# 130731_AriloRX_0_0.net
KiCad netlist of a schematic drawn in EAGLE
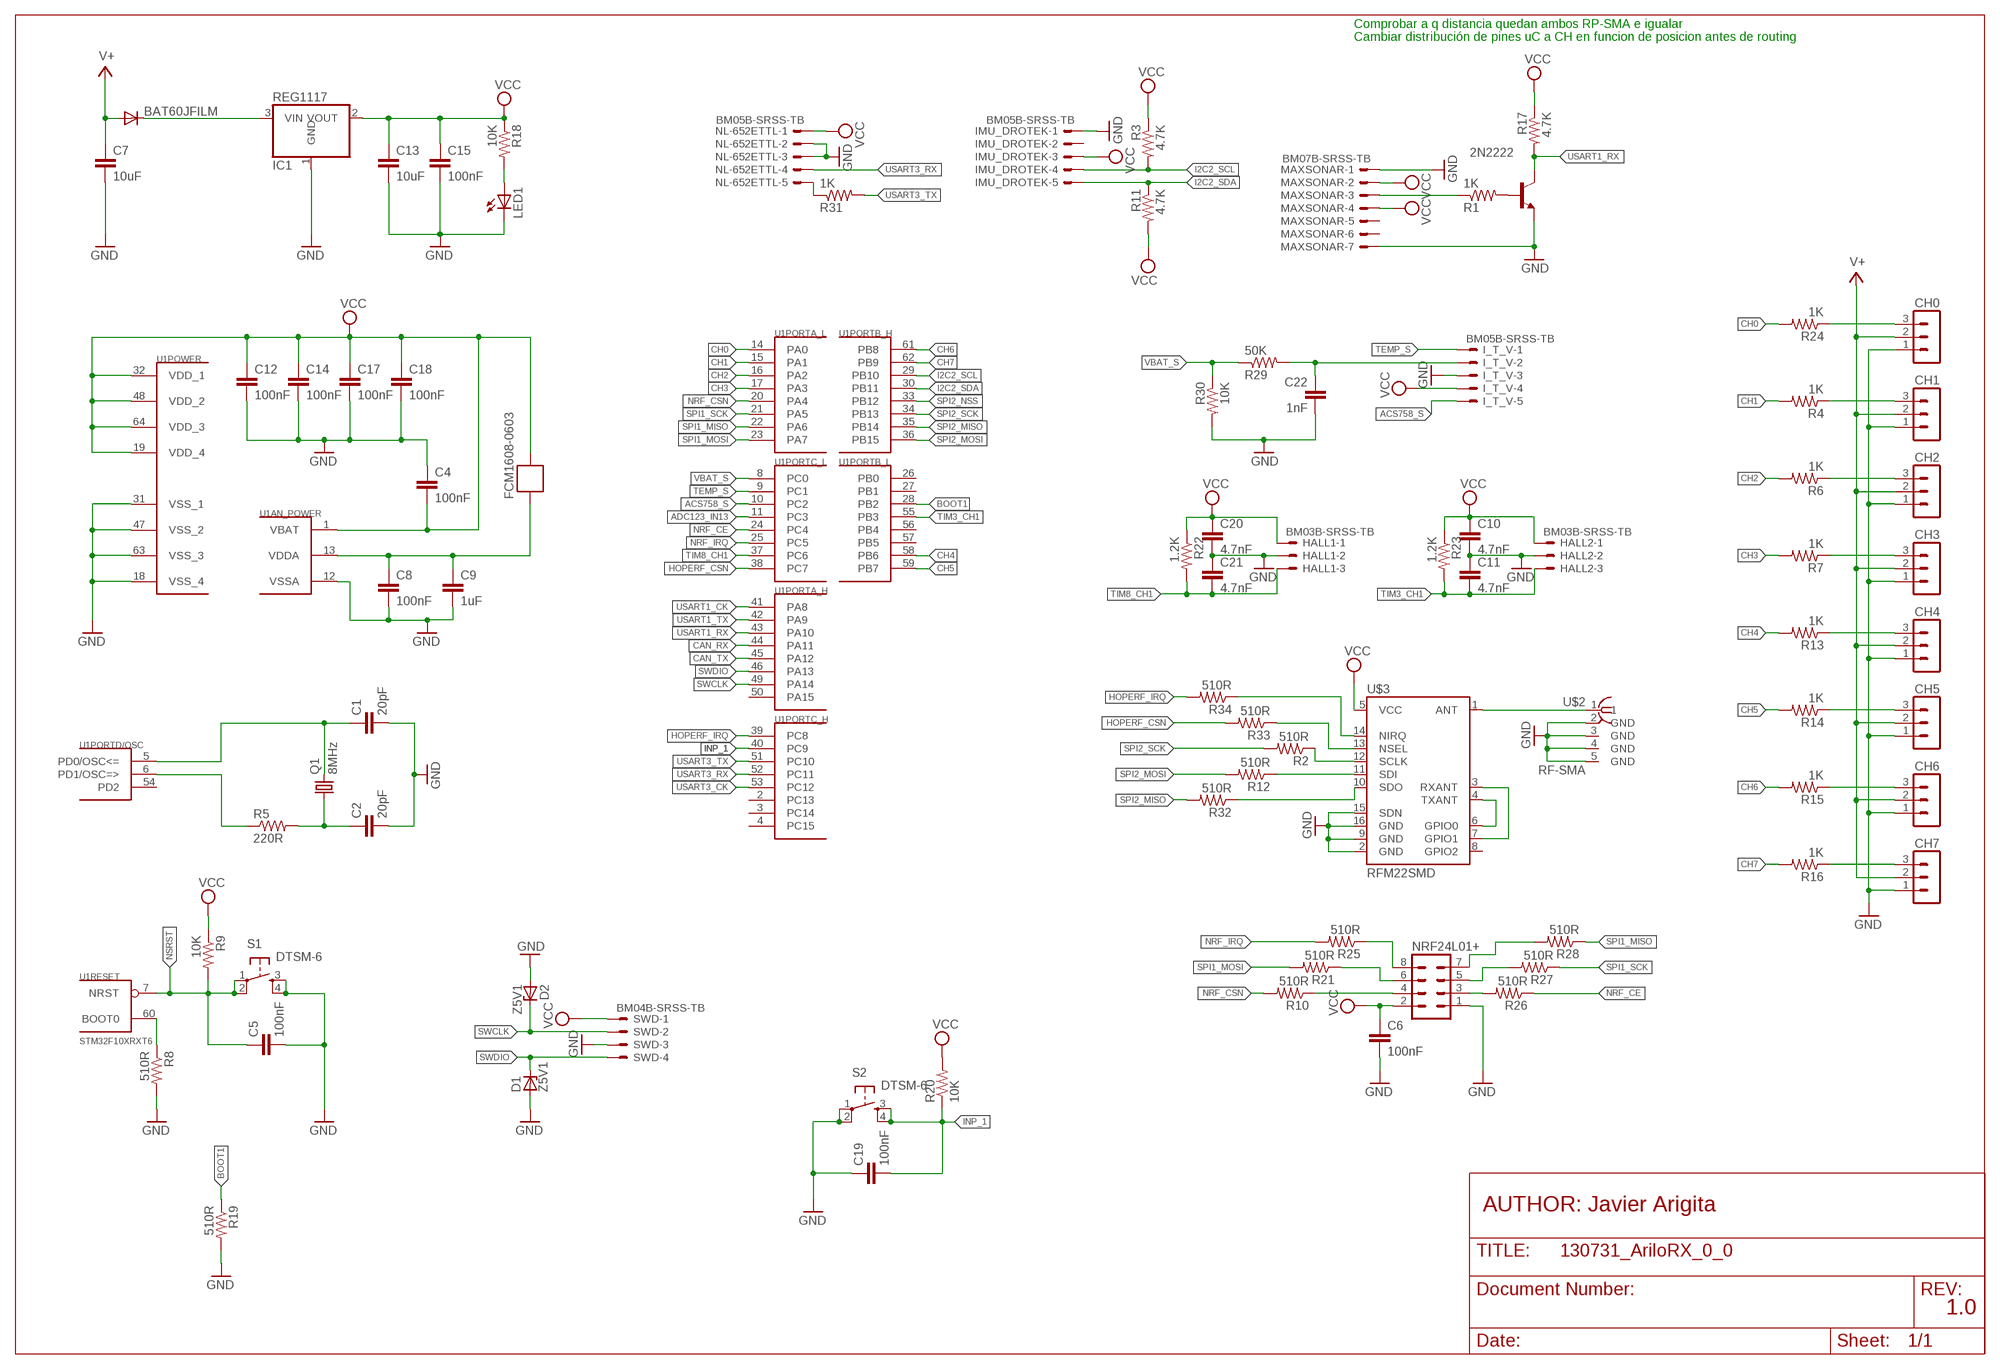
[diagram p0: schematic, sheet 1]

(export (version "E")
  (design (tool "Eeschema 10.0.6"))
  (components
    (comp (ref "2N2222")
      (value "MMBT2222ALT1-NPN-SOT23-BEC")
      (footprint "eagle-import:SOT23-BEC")
      (libsource (lib "eagle-import") (part "-NPN-SOT23-BECMMBT2222ALT1"))
    )
    (comp (ref "BAT60JFILM")
      (value "DIODE-SOD323-R")
      (footprint "eagle-import:SOD323-R")
      (libsource (lib "eagle-import") (part "DIODE-SOD323-R"))
    )
    (comp (ref "C1")
      (value "20pF")
      (footprint "eagle-import:C0805")
      (libsource (lib "eagle-import") (part "C-EUC0805"))
    )
    (comp (ref "C2")
      (value "20pF")
      (footprint "eagle-import:C0805")
      (libsource (lib "eagle-import") (part "C-EUC0805"))
    )
    (comp (ref "C4")
      (value "100nF")
      (footprint "eagle-import:C0805")
      (libsource (lib "eagle-import") (part "C-EUC0805"))
    )
    (comp (ref "C5")
      (value "100nF")
      (footprint "eagle-import:C0805")
      (libsource (lib "eagle-import") (part "C-EUC0805"))
    )
    (comp (ref "C6")
      (value "100nF")
      (footprint "eagle-import:C0805")
      (libsource (lib "eagle-import") (part "C-EUC0805"))
    )
    (comp (ref "C7")
      (value "10uF")
      (footprint "eagle-import:C3216")
      (libsource (lib "eagle-import") (part "resistor_C-EUC3216"))
    )
    (comp (ref "C8")
      (value "100nF")
      (footprint "eagle-import:C0805")
      (libsource (lib "eagle-import") (part "C-EUC0805"))
    )
    (comp (ref "C9")
      (value "1uF")
      (footprint "eagle-import:C3216")
      (libsource (lib "eagle-import") (part "resistor_C-EUC3216"))
    )
    (comp (ref "C10")
      (value "4.7nF")
      (footprint "eagle-import:C0805")
      (libsource (lib "eagle-import") (part "C-EUC0805"))
    )
    (comp (ref "C11")
      (value "4.7nF")
      (footprint "eagle-import:C0805")
      (libsource (lib "eagle-import") (part "C-EUC0805"))
    )
    (comp (ref "C12")
      (value "100nF")
      (footprint "eagle-import:C0805")
      (libsource (lib "eagle-import") (part "C-EUC0805"))
    )
    (comp (ref "C13")
      (value "10uF")
      (footprint "eagle-import:C3216")
      (libsource (lib "eagle-import") (part "resistor_C-EUC3216"))
    )
    (comp (ref "C14")
      (value "100nF")
      (footprint "eagle-import:C0805")
      (libsource (lib "eagle-import") (part "C-EUC0805"))
    )
    (comp (ref "C15")
      (value "100nF")
      (footprint "eagle-import:C0805")
      (libsource (lib "eagle-import") (part "C-EUC0805"))
    )
    (comp (ref "C17")
      (value "100nF")
      (footprint "eagle-import:C0805")
      (libsource (lib "eagle-import") (part "C-EUC0805"))
    )
    (comp (ref "C18")
      (value "100nF")
      (footprint "eagle-import:C0805")
      (libsource (lib "eagle-import") (part "C-EUC0805"))
    )
    (comp (ref "C19")
      (value "100nF")
      (footprint "eagle-import:C0805")
      (libsource (lib "eagle-import") (part "C-EUC0805"))
    )
    (comp (ref "C20")
      (value "4.7nF")
      (footprint "eagle-import:C0805")
      (libsource (lib "eagle-import") (part "C-EUC0805"))
    )
    (comp (ref "C21")
      (value "4.7nF")
      (footprint "eagle-import:C0805")
      (libsource (lib "eagle-import") (part "C-EUC0805"))
    )
    (comp (ref "C22")
      (value "1nF")
      (footprint "eagle-import:C0805")
      (libsource (lib "eagle-import") (part "C-EUC0805"))
    )
    (comp (ref "CH0")
      (value "MA03-1")
      (footprint "eagle-import:MA03-1")
      (libsource (lib "eagle-import") (part "MA03-1"))
    )
    (comp (ref "CH1")
      (value "MA03-1")
      (footprint "eagle-import:MA03-1")
      (libsource (lib "eagle-import") (part "MA03-1"))
    )
    (comp (ref "CH2")
      (value "MA03-1")
      (footprint "eagle-import:MA03-1")
      (libsource (lib "eagle-import") (part "MA03-1"))
    )
    (comp (ref "CH3")
      (value "MA03-1")
      (footprint "eagle-import:MA03-1")
      (libsource (lib "eagle-import") (part "MA03-1"))
    )
    (comp (ref "CH4")
      (value "MA03-1")
      (footprint "eagle-import:MA03-1")
      (libsource (lib "eagle-import") (part "MA03-1"))
    )
    (comp (ref "CH5")
      (value "MA03-1")
      (footprint "eagle-import:MA03-1")
      (libsource (lib "eagle-import") (part "MA03-1"))
    )
    (comp (ref "CH6")
      (value "MA03-1")
      (footprint "eagle-import:MA03-1")
      (libsource (lib "eagle-import") (part "MA03-1"))
    )
    (comp (ref "CH7")
      (value "MA03-1")
      (footprint "eagle-import:MA03-1")
      (libsource (lib "eagle-import") (part "MA03-1"))
    )
    (comp (ref "D1")
      (value "Z5V1")
      (footprint "eagle-import:SOD80C")
      (libsource (lib "eagle-import") (part "ZENER-DIODESOD80C"))
    )
    (comp (ref "D2")
      (value "Z5V1")
      (footprint "eagle-import:SOD80C")
      (libsource (lib "eagle-import") (part "ZENER-DIODESOD80C"))
    )
    (comp (ref "FCM1608-0603")
      (value "FERRITE-BEAD")
      (footprint "eagle-import:R0603")
      (libsource (lib "eagle-import") (part "FERRITE-BEAD"))
    )
    (comp (ref "HALL1")
      (value "BM03B-SRSS-TB")
      (footprint "eagle-import:BM03B-SRSS-TB")
      (libsource (lib "eagle-import") (part "?M03B-SRSS-TBB"))
    )
    (comp (ref "HALL2")
      (value "BM03B-SRSS-TB")
      (footprint "eagle-import:BM03B-SRSS-TB")
      (libsource (lib "eagle-import") (part "?M03B-SRSS-TBB"))
    )
    (comp (ref "IC1")
      (value "REG1117")
      (footprint "eagle-import:SOT223")
      (libsource (lib "eagle-import") (part "REG1117"))
    )
    (comp (ref "IMU_DROTEK")
      (value "BM05B-SRSS-TB")
      (footprint "eagle-import:BM05B-SRSS-TB")
      (libsource (lib "eagle-import") (part "?M05B-SRSS-TBB"))
    )
    (comp (ref "I_T_V")
      (value "BM05B-SRSS-TB")
      (footprint "eagle-import:BM05B-SRSS-TB")
      (libsource (lib "eagle-import") (part "?M05B-SRSS-TBB"))
    )
    (comp (ref "LED1")
      (value "LED0805")
      (footprint "eagle-import:CHIPLED_0805")
      (libsource (lib "eagle-import") (part "LED0805"))
    )
    (comp (ref "MAXSONAR")
      (value "BM07B-SRSS-TB")
      (footprint "eagle-import:BM07B-SRSS-TB")
      (libsource (lib "eagle-import") (part "?M07B-SRSS-TBB"))
    )
    (comp (ref "NL-652ETTL")
      (value "BM05B-SRSS-TB")
      (footprint "eagle-import:BM05B-SRSS-TB")
      (libsource (lib "eagle-import") (part "?M05B-SRSS-TBB"))
    )
    (comp (ref "NRF24L01+")
      (value "MA04-2")
      (footprint "eagle-import:MA04-2")
      (libsource (lib "eagle-import") (part "MA04-2"))
    )
    (comp (ref "Q1")
      (value "8MHz")
      (footprint "eagle-import:SM49")
      (libsource (lib "eagle-import") (part "CRYSTALSM49"))
    )
    (comp (ref "R1")
      (value "1K")
      (footprint "eagle-import:R0805")
      (libsource (lib "eagle-import") (part "RESISTOR0805"))
    )
    (comp (ref "R2")
      (value "510R")
      (footprint "eagle-import:R0805")
      (libsource (lib "eagle-import") (part "RESISTOR0805"))
    )
    (comp (ref "R3")
      (value "4.7K")
      (footprint "eagle-import:R0805")
      (libsource (lib "eagle-import") (part "RESISTOR0805"))
    )
    (comp (ref "R4")
      (value "1K")
      (footprint "eagle-import:R0805")
      (libsource (lib "eagle-import") (part "RESISTOR0805"))
    )
    (comp (ref "R5")
      (value "220R")
      (footprint "eagle-import:R0805")
      (libsource (lib "eagle-import") (part "RESISTOR0805"))
    )
    (comp (ref "R6")
      (value "1K")
      (footprint "eagle-import:R0805")
      (libsource (lib "eagle-import") (part "RESISTOR0805"))
    )
    (comp (ref "R7")
      (value "1K")
      (footprint "eagle-import:R0805")
      (libsource (lib "eagle-import") (part "RESISTOR0805"))
    )
    (comp (ref "R8")
      (value "510R")
      (footprint "eagle-import:R0805")
      (libsource (lib "eagle-import") (part "RESISTOR0805"))
    )
    (comp (ref "R9")
      (value "10K")
      (footprint "eagle-import:R0805")
      (libsource (lib "eagle-import") (part "RESISTOR0805"))
    )
    (comp (ref "R10")
      (value "510R")
      (footprint "eagle-import:R0805")
      (libsource (lib "eagle-import") (part "RESISTOR0805"))
    )
    (comp (ref "R11")
      (value "4.7K")
      (footprint "eagle-import:R0805")
      (libsource (lib "eagle-import") (part "RESISTOR0805"))
    )
    (comp (ref "R12")
      (value "510R")
      (footprint "eagle-import:R0805")
      (libsource (lib "eagle-import") (part "RESISTOR0805"))
    )
    (comp (ref "R13")
      (value "1K")
      (footprint "eagle-import:R0805")
      (libsource (lib "eagle-import") (part "RESISTOR0805"))
    )
    (comp (ref "R14")
      (value "1K")
      (footprint "eagle-import:R0805")
      (libsource (lib "eagle-import") (part "RESISTOR0805"))
    )
    (comp (ref "R15")
      (value "1K")
      (footprint "eagle-import:R0805")
      (libsource (lib "eagle-import") (part "RESISTOR0805"))
    )
    (comp (ref "R16")
      (value "1K")
      (footprint "eagle-import:R0805")
      (libsource (lib "eagle-import") (part "RESISTOR0805"))
    )
    (comp (ref "R17")
      (value "4.7K")
      (footprint "eagle-import:R0805")
      (libsource (lib "eagle-import") (part "RESISTOR0805"))
    )
    (comp (ref "R18")
      (value "10K")
      (footprint "eagle-import:R0805")
      (libsource (lib "eagle-import") (part "RESISTOR0805"))
    )
    (comp (ref "R19")
      (value "510R")
      (footprint "eagle-import:R0805")
      (libsource (lib "eagle-import") (part "RESISTOR0805"))
    )
    (comp (ref "R20")
      (value "10K")
      (footprint "eagle-import:R0805")
      (libsource (lib "eagle-import") (part "RESISTOR0805"))
    )
    (comp (ref "R21")
      (value "510R")
      (footprint "eagle-import:R0805")
      (libsource (lib "eagle-import") (part "RESISTOR0805"))
    )
    (comp (ref "R22")
      (value "1.2K")
      (footprint "eagle-import:R0805")
      (libsource (lib "eagle-import") (part "RESISTOR0805"))
    )
    (comp (ref "R23")
      (value "1.2K")
      (footprint "eagle-import:R0805")
      (libsource (lib "eagle-import") (part "RESISTOR0805"))
    )
    (comp (ref "R24")
      (value "1K")
      (footprint "eagle-import:R0805")
      (libsource (lib "eagle-import") (part "RESISTOR0805"))
    )
    (comp (ref "R25")
      (value "510R")
      (footprint "eagle-import:R0805")
      (libsource (lib "eagle-import") (part "RESISTOR0805"))
    )
    (comp (ref "R26")
      (value "510R")
      (footprint "eagle-import:R0805")
      (libsource (lib "eagle-import") (part "RESISTOR0805"))
    )
    (comp (ref "R27")
      (value "510R")
      (footprint "eagle-import:R0805")
      (libsource (lib "eagle-import") (part "RESISTOR0805"))
    )
    (comp (ref "R28")
      (value "510R")
      (footprint "eagle-import:R0805")
      (libsource (lib "eagle-import") (part "RESISTOR0805"))
    )
    (comp (ref "R29")
      (value "50K")
      (footprint "eagle-import:R0805")
      (libsource (lib "eagle-import") (part "RESISTOR0805"))
    )
    (comp (ref "R30")
      (value "10K")
      (footprint "eagle-import:R0805")
      (libsource (lib "eagle-import") (part "RESISTOR0805"))
    )
    (comp (ref "R31")
      (value "1K")
      (footprint "eagle-import:R0805")
      (libsource (lib "eagle-import") (part "RESISTOR0805"))
    )
    (comp (ref "R32")
      (value "510R")
      (footprint "eagle-import:R0805")
      (libsource (lib "eagle-import") (part "RESISTOR0805"))
    )
    (comp (ref "R33")
      (value "510R")
      (footprint "eagle-import:R0805")
      (libsource (lib "eagle-import") (part "RESISTOR0805"))
    )
    (comp (ref "R34")
      (value "510R")
      (footprint "eagle-import:R0805")
      (libsource (lib "eagle-import") (part "RESISTOR0805"))
    )
    (comp (ref "S1")
      (value "DTSM-6")
      (footprint "eagle-import:DTSM-6")
      (libsource (lib "eagle-import") (part "DTSM-6"))
    )
    (comp (ref "S2")
      (value "DTSM-6")
      (footprint "eagle-import:DTSM-6")
      (libsource (lib "eagle-import") (part "DTSM-6"))
    )
    (comp (ref "SWD")
      (value "BM04B-SRSS-TB")
      (footprint "eagle-import:BM04B-SRSS-TB")
      (libsource (lib "eagle-import") (part "?M04B-SRSS-TBB"))
    )
    (comp (ref "U$2")
      (value "RF-SMA")
      (footprint "eagle-import:BU-SMA-H")
      (libsource (lib "eagle-import") (part "RF-SMA"))
    )
    (comp (ref "U$3")
      (value "RFM22SMD")
      (footprint "eagle-import:RFM22-XXX-S2")
      (libsource (lib "eagle-import") (part "RFM22SMD"))
    )
    (comp (ref "U1")
      (value "STM32F10XRXT6")
      (footprint "eagle-import:TQFP64")
      (libsource (lib "eagle-import") (part "STM32F10XRXT6"))
    )
  )
  (nets
    (net (code "1") (name "ACS758_S") (class "Default")
      (node (ref "I_T_V") (pin "5") (pinfunction "S_5") (pintype "passive"))
      (node (ref "U1") (pin "10") (pinfunction "PC2_10") (pintype "bidirectional"))
    )
    (net (code "2") (name "ADC123_IN13") (class "Default")
      (node (ref "U1") (pin "11") (pinfunction "PC3_11") (pintype "bidirectional"))
    )
    (net (code "3") (name "BOOT1") (class "Default")
      (node (ref "R19") (pin "1") (pinfunction "1_1") (pintype "passive"))
      (node (ref "U1") (pin "28") (pinfunction "PB2_28") (pintype "bidirectional"))
    )
    (net (code "4") (name "CAN_RX") (class "Default")
      (node (ref "U1") (pin "44") (pinfunction "PA11_44") (pintype "bidirectional"))
    )
    (net (code "5") (name "CAN_TX") (class "Default")
      (node (ref "U1") (pin "45") (pinfunction "PA12_45") (pintype "bidirectional"))
    )
    (net (code "6") (name "CH0") (class "Default")
      (node (ref "R24") (pin "2") (pinfunction "2_2") (pintype "passive"))
      (node (ref "U1") (pin "14") (pinfunction "PA0_14") (pintype "bidirectional"))
    )
    (net (code "7") (name "CH1") (class "Default")
      (node (ref "R4") (pin "2") (pinfunction "2_2") (pintype "passive"))
      (node (ref "U1") (pin "15") (pinfunction "PA1_15") (pintype "bidirectional"))
    )
    (net (code "8") (name "CH2") (class "Default")
      (node (ref "R6") (pin "2") (pinfunction "2_2") (pintype "passive"))
      (node (ref "U1") (pin "16") (pinfunction "PA2_16") (pintype "bidirectional"))
    )
    (net (code "9") (name "CH3") (class "Default")
      (node (ref "R7") (pin "2") (pinfunction "2_2") (pintype "passive"))
      (node (ref "U1") (pin "17") (pinfunction "PA3_17") (pintype "bidirectional"))
    )
    (net (code "10") (name "CH4") (class "Default")
      (node (ref "R13") (pin "2") (pinfunction "2_2") (pintype "passive"))
      (node (ref "U1") (pin "58") (pinfunction "PB6_58") (pintype "bidirectional"))
    )
    (net (code "11") (name "CH5") (class "Default")
      (node (ref "R14") (pin "2") (pinfunction "2_2") (pintype "passive"))
      (node (ref "U1") (pin "59") (pinfunction "PB7_59") (pintype "bidirectional"))
    )
    (net (code "12") (name "CH6") (class "Default")
      (node (ref "R15") (pin "2") (pinfunction "2_2") (pintype "passive"))
      (node (ref "U1") (pin "61") (pinfunction "PB8_61") (pintype "bidirectional"))
    )
    (net (code "13") (name "CH7") (class "Default")
      (node (ref "R16") (pin "2") (pinfunction "2_2") (pintype "passive"))
      (node (ref "U1") (pin "62") (pinfunction "PB9_62") (pintype "bidirectional"))
    )
    (net (code "14") (name "GND") (class "Default")
      (node (ref "2N2222") (pin "E") (pinfunction "E_E") (pintype "passive"))
      (node (ref "C1") (pin "2") (pinfunction "2_2") (pintype "passive"))
      (node (ref "C10") (pin "2") (pinfunction "2_2") (pintype "passive"))
      (node (ref "C11") (pin "1") (pinfunction "1_1") (pintype "passive"))
      (node (ref "C12") (pin "2") (pinfunction "2_2") (pintype "passive"))
      (node (ref "C13") (pin "2") (pinfunction "2_2") (pintype "passive"))
      (node (ref "C14") (pin "2") (pinfunction "2_2") (pintype "passive"))
      (node (ref "C15") (pin "2") (pinfunction "2_2") (pintype "passive"))
      (node (ref "C17") (pin "2") (pinfunction "2_2") (pintype "passive"))
      (node (ref "C18") (pin "2") (pinfunction "2_2") (pintype "passive"))
      (node (ref "C19") (pin "1") (pinfunction "1_1") (pintype "passive"))
      (node (ref "C2") (pin "2") (pinfunction "2_2") (pintype "passive"))
      (node (ref "C20") (pin "2") (pinfunction "2_2") (pintype "passive"))
      (node (ref "C21") (pin "1") (pinfunction "1_1") (pintype "passive"))
      (node (ref "C22") (pin "2") (pinfunction "2_2") (pintype "passive"))
      (node (ref "C4") (pin "1") (pinfunction "1_1") (pintype "passive"))
      (node (ref "C5") (pin "2") (pinfunction "2_2") (pintype "passive"))
      (node (ref "C6") (pin "2") (pinfunction "2_2") (pintype "passive"))
      (node (ref "C7") (pin "2") (pinfunction "2_2") (pintype "passive"))
      (node (ref "C8") (pin "2") (pinfunction "2_2") (pintype "passive"))
      (node (ref "C9") (pin "2") (pinfunction "2_2") (pintype "passive"))
      (node (ref "CH0") (pin "1") (pinfunction "1_1") (pintype "passive"))
      (node (ref "CH1") (pin "1") (pinfunction "1_1") (pintype "passive"))
      (node (ref "CH2") (pin "1") (pinfunction "1_1") (pintype "passive"))
      (node (ref "CH3") (pin "1") (pinfunction "1_1") (pintype "passive"))
      (node (ref "CH4") (pin "1") (pinfunction "1_1") (pintype "passive"))
      (node (ref "CH5") (pin "1") (pinfunction "1_1") (pintype "passive"))
      (node (ref "CH6") (pin "1") (pinfunction "1_1") (pintype "passive"))
      (node (ref "CH7") (pin "1") (pinfunction "1_1") (pintype "passive"))
      (node (ref "D1") (pin "A") (pinfunction "A_A") (pintype "passive"))
      (node (ref "D2") (pin "A") (pinfunction "A_A") (pintype "passive"))
      (node (ref "HALL1") (pin "2") (pinfunction "S_2") (pintype "passive"))
      (node (ref "HALL2") (pin "2") (pinfunction "S_2") (pintype "passive"))
      (node (ref "IC1") (pin "1") (pinfunction "GND_1") (pintype "power_in"))
      (node (ref "IMU_DROTEK") (pin "1") (pinfunction "S_1") (pintype "passive"))
      (node (ref "I_T_V") (pin "3") (pinfunction "S_3") (pintype "passive"))
      (node (ref "LED1") (pin "C") (pinfunction "C_C") (pintype "passive"))
      (node (ref "MAXSONAR") (pin "1") (pinfunction "S_1") (pintype "passive"))
      (node (ref "MAXSONAR") (pin "7") (pinfunction "S_7") (pintype "passive"))
      (node (ref "NL-652ETTL") (pin "2") (pinfunction "S_2") (pintype "passive"))
      (node (ref "NL-652ETTL") (pin "3") (pinfunction "S_3") (pintype "passive"))
      (node (ref "NRF24L01+") (pin "1") (pinfunction "1_1") (pintype "passive"))
      (node (ref "R19") (pin "2") (pinfunction "2_2") (pintype "passive"))
      (node (ref "R30") (pin "2") (pinfunction "2_2") (pintype "passive"))
      (node (ref "R8") (pin "2") (pinfunction "2_2") (pintype "passive"))
      (node (ref "S1") (pin "3") (pinfunction "3_3") (pintype "passive"))
      (node (ref "S1") (pin "4") (pinfunction "4_4") (pintype "passive"))
      (node (ref "S2") (pin "1") (pinfunction "1_1") (pintype "passive"))
      (node (ref "S2") (pin "2") (pinfunction "2_2") (pintype "passive"))
      (node (ref "SWD") (pin "3") (pinfunction "S_3") (pintype "passive"))
      (node (ref "U$2") (pin "2") (pinfunction "GND_2") (pintype "power_in"))
      (node (ref "U$2") (pin "3") (pinfunction "GND_3") (pintype "bidirectional"))
      (node (ref "U$2") (pin "4") (pinfunction "GND_4") (pintype "bidirectional"))
      (node (ref "U$2") (pin "5") (pinfunction "GND_5") (pintype "bidirectional"))
      (node (ref "U$3") (pin "15") (pinfunction "SDN_15") (pintype "input"))
      (node (ref "U$3") (pin "16") (pinfunction "GND_16") (pintype "power_in"))
      (node (ref "U$3") (pin "2") (pinfunction "GND_2") (pintype "power_in"))
      (node (ref "U$3") (pin "9") (pinfunction "GND_9") (pintype "power_in"))
      (node (ref "U1") (pin "12") (pinfunction "VSSA_12") (pintype "power_in"))
      (node (ref "U1") (pin "18") (pinfunction "VSS_4_18") (pintype "power_in"))
      (node (ref "U1") (pin "31") (pinfunction "VSS_1_31") (pintype "power_in"))
      (node (ref "U1") (pin "47") (pinfunction "VSS_2_47") (pintype "power_in"))
      (node (ref "U1") (pin "63") (pinfunction "VSS_3_63") (pintype "power_in"))
    )
    (net (code "15") (name "HOPERF_CSN") (class "Default")
      (node (ref "R33") (pin "2") (pinfunction "2_2") (pintype "passive"))
      (node (ref "U1") (pin "38") (pinfunction "PC7_38") (pintype "bidirectional"))
    )
    (net (code "16") (name "HOPERF_IRQ") (class "Default")
      (node (ref "R34") (pin "2") (pinfunction "2_2") (pintype "passive"))
      (node (ref "U1") (pin "39") (pinfunction "PC8_39") (pintype "bidirectional"))
    )
    (net (code "17") (name "I2C2_SCL") (class "Default")
      (node (ref "IMU_DROTEK") (pin "4") (pinfunction "S_4") (pintype "passive"))
      (node (ref "R3") (pin "2") (pinfunction "2_2") (pintype "passive"))
      (node (ref "U1") (pin "29") (pinfunction "PB10_29") (pintype "bidirectional"))
    )
    (net (code "18") (name "I2C2_SDA") (class "Default")
      (node (ref "IMU_DROTEK") (pin "5") (pinfunction "S_5") (pintype "passive"))
      (node (ref "R11") (pin "1") (pinfunction "1_1") (pintype "passive"))
      (node (ref "U1") (pin "30") (pinfunction "PB11_30") (pintype "bidirectional"))
    )
    (net (code "19") (name "INP_1") (class "Default")
      (node (ref "C19") (pin "2") (pinfunction "2_2") (pintype "passive"))
      (node (ref "R20") (pin "1") (pinfunction "1_1") (pintype "passive"))
      (node (ref "S2") (pin "3") (pinfunction "3_3") (pintype "passive"))
      (node (ref "S2") (pin "4") (pinfunction "4_4") (pintype "passive"))
      (node (ref "U1") (pin "40") (pinfunction "PC9_40") (pintype "bidirectional"))
    )
    (net (code "20") (name "NRF_CE") (class "Default")
      (node (ref "R26") (pin "1") (pinfunction "1_1") (pintype "passive"))
      (node (ref "U1") (pin "24") (pinfunction "PC4_24") (pintype "bidirectional"))
    )
    (net (code "21") (name "NRF_CSN") (class "Default")
      (node (ref "R10") (pin "2") (pinfunction "2_2") (pintype "passive"))
      (node (ref "U1") (pin "20") (pinfunction "PA4_20") (pintype "bidirectional"))
    )
    (net (code "22") (name "NRF_IRQ") (class "Default")
      (node (ref "R25") (pin "2") (pinfunction "2_2") (pintype "passive"))
      (node (ref "U1") (pin "25") (pinfunction "PC5_25") (pintype "bidirectional"))
    )
    (net (code "23") (name "NSRST") (class "Default")
      (node (ref "C5") (pin "1") (pinfunction "1_1") (pintype "passive"))
      (node (ref "R9") (pin "2") (pinfunction "2_2") (pintype "passive"))
      (node (ref "S1") (pin "1") (pinfunction "1_1") (pintype "passive"))
      (node (ref "S1") (pin "2") (pinfunction "2_2") (pintype "passive"))
      (node (ref "U1") (pin "7") (pinfunction "NRST_7") (pintype "input"))
    )
    (net (code "24") (name "Net-(2N2222-PadB)") (class "Default")
      (node (ref "2N2222") (pin "B") (pinfunction "B_B") (pintype "passive"))
      (node (ref "R1") (pin "2") (pinfunction "2_2") (pintype "passive"))
    )
    (net (code "25") (name "Net-(C2-Pad1)") (class "Default")
      (node (ref "C2") (pin "1") (pinfunction "1_1") (pintype "passive"))
      (node (ref "Q1") (pin "1") (pinfunction "1_1") (pintype "passive"))
      (node (ref "R5") (pin "2") (pinfunction "2_2") (pintype "passive"))
    )
    (net (code "26") (name "Net-(CH0-Pad3)") (class "Default")
      (node (ref "CH0") (pin "3") (pinfunction "3_3") (pintype "passive"))
      (node (ref "R24") (pin "1") (pinfunction "1_1") (pintype "passive"))
    )
    (net (code "27") (name "Net-(CH1-Pad3)") (class "Default")
      (node (ref "CH1") (pin "3") (pinfunction "3_3") (pintype "passive"))
      (node (ref "R4") (pin "1") (pinfunction "1_1") (pintype "passive"))
    )
    (net (code "28") (name "Net-(CH2-Pad3)") (class "Default")
      (node (ref "CH2") (pin "3") (pinfunction "3_3") (pintype "passive"))
      (node (ref "R6") (pin "1") (pinfunction "1_1") (pintype "passive"))
    )
    (net (code "29") (name "Net-(CH3-Pad3)") (class "Default")
      (node (ref "CH3") (pin "3") (pinfunction "3_3") (pintype "passive"))
      (node (ref "R7") (pin "1") (pinfunction "1_1") (pintype "passive"))
    )
    (net (code "30") (name "Net-(CH4-Pad3)") (class "Default")
      (node (ref "CH4") (pin "3") (pinfunction "3_3") (pintype "passive"))
      (node (ref "R13") (pin "1") (pinfunction "1_1") (pintype "passive"))
    )
    (net (code "31") (name "Net-(CH5-Pad3)") (class "Default")
      (node (ref "CH5") (pin "3") (pinfunction "3_3") (pintype "passive"))
      (node (ref "R14") (pin "1") (pinfunction "1_1") (pintype "passive"))
    )
    (net (code "32") (name "Net-(CH6-Pad3)") (class "Default")
      (node (ref "CH6") (pin "3") (pinfunction "3_3") (pintype "passive"))
      (node (ref "R15") (pin "1") (pinfunction "1_1") (pintype "passive"))
    )
    (net (code "33") (name "Net-(CH7-Pad3)") (class "Default")
      (node (ref "CH7") (pin "3") (pinfunction "3_3") (pintype "passive"))
      (node (ref "R16") (pin "1") (pinfunction "1_1") (pintype "passive"))
    )
    (net (code "34") (name "Net-(FCM1608-0603-P$2)") (class "Default")
      (node (ref "C8") (pin "1") (pinfunction "1_1") (pintype "passive"))
      (node (ref "C9") (pin "1") (pinfunction "1_1") (pintype "passive"))
      (node (ref "FCM1608-0603") (pin "2") (pinfunction "P$2_2") (pintype "bidirectional"))
      (node (ref "U1") (pin "13") (pinfunction "VDDA_13") (pintype "power_in"))
    )
    (net (code "35") (name "Net-(IC1-VIN)") (class "Default")
      (node (ref "BAT60JFILM") (pin "C") (pinfunction "C_C") (pintype "passive"))
      (node (ref "IC1") (pin "3") (pinfunction "VIN_3") (pintype "input"))
    )
    (net (code "36") (name "Net-(I_T_VB-S)") (class "Default")
      (node (ref "C22") (pin "1") (pinfunction "1_1") (pintype "passive"))
      (node (ref "I_T_V") (pin "2") (pinfunction "S_2") (pintype "passive"))
      (node (ref "R29") (pin "2") (pinfunction "2_2") (pintype "passive"))
    )
    (net (code "37") (name "Net-(LED1-PadA)") (class "Default")
      (node (ref "LED1") (pin "A") (pinfunction "A_A") (pintype "passive"))
      (node (ref "R18") (pin "2") (pinfunction "2_2") (pintype "passive"))
    )
    (net (code "38") (name "Net-(MAXSONARC-S)") (class "Default")
      (node (ref "MAXSONAR") (pin "3") (pinfunction "S_3") (pintype "passive"))
      (node (ref "R1") (pin "1") (pinfunction "1_1") (pintype "passive"))
    )
    (net (code "39") (name "Net-(NL-652ETTLE-S)") (class "Default")
      (node (ref "NL-652ETTL") (pin "5") (pinfunction "S_5") (pintype "passive"))
      (node (ref "R31") (pin "1") (pinfunction "1_1") (pintype "passive"))
    )
    (net (code "40") (name "Net-(NRF24L01+-Pad3)") (class "Default")
      (node (ref "NRF24L01+") (pin "3") (pinfunction "3_3") (pintype "passive"))
      (node (ref "R26") (pin "2") (pinfunction "2_2") (pintype "passive"))
    )
    (net (code "41") (name "Net-(NRF24L01+-Pad4)") (class "Default")
      (node (ref "NRF24L01+") (pin "4") (pinfunction "4_4") (pintype "passive"))
      (node (ref "R10") (pin "1") (pinfunction "1_1") (pintype "passive"))
    )
    (net (code "42") (name "Net-(NRF24L01+-Pad5)") (class "Default")
      (node (ref "NRF24L01+") (pin "5") (pinfunction "5_5") (pintype "passive"))
      (node (ref "R27") (pin "2") (pinfunction "2_2") (pintype "passive"))
    )
    (net (code "43") (name "Net-(NRF24L01+-Pad6)") (class "Default")
      (node (ref "NRF24L01+") (pin "6") (pinfunction "6_6") (pintype "passive"))
      (node (ref "R21") (pin "1") (pinfunction "1_1") (pintype "passive"))
    )
    (net (code "44") (name "Net-(NRF24L01+-Pad7)") (class "Default")
      (node (ref "NRF24L01+") (pin "7") (pinfunction "7_7") (pintype "passive"))
      (node (ref "R28") (pin "2") (pinfunction "2_2") (pintype "passive"))
    )
    (net (code "45") (name "Net-(NRF24L01+-Pad8)") (class "Default")
      (node (ref "NRF24L01+") (pin "8") (pinfunction "8_8") (pintype "passive"))
      (node (ref "R25") (pin "1") (pinfunction "1_1") (pintype "passive"))
    )
    (net (code "46") (name "Net-(U$3-ANT)") (class "Default")
      (node (ref "U$2") (pin "1") (pinfunction "1_1") (pintype "passive"))
      (node (ref "U$3") (pin "1") (pinfunction "ANT_1") (pintype "bidirectional"))
    )
    (net (code "47") (name "Net-(U$3-GPIO0)") (class "Default")
      (node (ref "U$3") (pin "4") (pinfunction "TXANT_4") (pintype "input"))
      (node (ref "U$3") (pin "6") (pinfunction "GPIO0_6") (pintype "bidirectional"))
    )
    (net (code "48") (name "Net-(U$3-GPIO1)") (class "Default")
      (node (ref "U$3") (pin "3") (pinfunction "RXANT_3") (pintype "input"))
      (node (ref "U$3") (pin "7") (pinfunction "GPIO1_7") (pintype "bidirectional"))
    )
    (net (code "49") (name "Net-(U$3-NIRQ)") (class "Default")
      (node (ref "R34") (pin "1") (pinfunction "1_1") (pintype "passive"))
      (node (ref "U$3") (pin "14") (pinfunction "NIRQ_14") (pintype "output"))
    )
    (net (code "50") (name "Net-(U$3-NSEL)") (class "Default")
      (node (ref "R33") (pin "1") (pinfunction "1_1") (pintype "passive"))
      (node (ref "U$3") (pin "13") (pinfunction "NSEL_13") (pintype "input"))
    )
    (net (code "51") (name "Net-(U$3-SCLK)") (class "Default")
      (node (ref "R2") (pin "1") (pinfunction "1_1") (pintype "passive"))
      (node (ref "U$3") (pin "12") (pinfunction "SCLK_12") (pintype "input"))
    )
    (net (code "52") (name "Net-(U$3-SDI)") (class "Default")
      (node (ref "R12") (pin "1") (pinfunction "1_1") (pintype "passive"))
      (node (ref "U$3") (pin "11") (pinfunction "SDI_11") (pintype "input"))
    )
    (net (code "53") (name "Net-(U$3-SDO)") (class "Default")
      (node (ref "R32") (pin "1") (pinfunction "1_1") (pintype "passive"))
      (node (ref "U$3") (pin "10") (pinfunction "SDO_10") (pintype "output"))
    )
    (net (code "54") (name "Net-(U1H-PD0{slash}OSC<=)") (class "Default")
      (node (ref "C1") (pin "1") (pinfunction "1_1") (pintype "passive"))
      (node (ref "Q1") (pin "2") (pinfunction "2_2") (pintype "passive"))
      (node (ref "U1") (pin "5") (pinfunction "PD0/OSC<=_5") (pintype "bidirectional"))
    )
    (net (code "55") (name "Net-(U1H-PD1{slash}OSC=>)") (class "Default")
      (node (ref "R5") (pin "1") (pinfunction "1_1") (pintype "passive"))
      (node (ref "U1") (pin "6") (pinfunction "PD1/OSC=>_6") (pintype "bidirectional"))
    )
    (net (code "56") (name "Net-(U1J-BOOT0)") (class "Default")
      (node (ref "R8") (pin "1") (pinfunction "1_1") (pintype "passive"))
      (node (ref "U1") (pin "60") (pinfunction "BOOT0_60") (pintype "input"))
    )
    (net (code "57") (name "SPI1_MISO") (class "Default")
      (node (ref "R28") (pin "1") (pinfunction "1_1") (pintype "passive"))
      (node (ref "U1") (pin "22") (pinfunction "PA6_22") (pintype "bidirectional"))
    )
    (net (code "58") (name "SPI1_MOSI") (class "Default")
      (node (ref "R21") (pin "2") (pinfunction "2_2") (pintype "passive"))
      (node (ref "U1") (pin "23") (pinfunction "PA7_23") (pintype "bidirectional"))
    )
    (net (code "59") (name "SPI1_SCK") (class "Default")
      (node (ref "R27") (pin "1") (pinfunction "1_1") (pintype "passive"))
      (node (ref "U1") (pin "21") (pinfunction "PA5_21") (pintype "bidirectional"))
    )
    (net (code "60") (name "SPI2_MISO") (class "Default")
      (node (ref "R32") (pin "2") (pinfunction "2_2") (pintype "passive"))
      (node (ref "U1") (pin "35") (pinfunction "PB14_35") (pintype "bidirectional"))
    )
    (net (code "61") (name "SPI2_MOSI") (class "Default")
      (node (ref "R12") (pin "2") (pinfunction "2_2") (pintype "passive"))
      (node (ref "U1") (pin "36") (pinfunction "PB15_36") (pintype "bidirectional"))
    )
    (net (code "62") (name "SPI2_NSS") (class "Default")
      (node (ref "U1") (pin "33") (pinfunction "PB12_33") (pintype "bidirectional"))
    )
    (net (code "63") (name "SPI2_SCK") (class "Default")
      (node (ref "R2") (pin "2") (pinfunction "2_2") (pintype "passive"))
      (node (ref "U1") (pin "34") (pinfunction "PB13_34") (pintype "bidirectional"))
    )
    (net (code "64") (name "SWCLK") (class "Default")
      (node (ref "D2") (pin "C") (pinfunction "C_C") (pintype "passive"))
      (node (ref "SWD") (pin "2") (pinfunction "S_2") (pintype "passive"))
      (node (ref "U1") (pin "49") (pinfunction "PA14_49") (pintype "bidirectional"))
    )
    (net (code "65") (name "SWDIO") (class "Default")
      (node (ref "D1") (pin "C") (pinfunction "C_C") (pintype "passive"))
      (node (ref "SWD") (pin "4") (pinfunction "S_4") (pintype "passive"))
      (node (ref "U1") (pin "46") (pinfunction "PA13_46") (pintype "bidirectional"))
    )
    (net (code "66") (name "TEMP_S") (class "Default")
      (node (ref "I_T_V") (pin "1") (pinfunction "S_1") (pintype "passive"))
      (node (ref "U1") (pin "9") (pinfunction "PC1_9") (pintype "bidirectional"))
    )
    (net (code "67") (name "TIM3_CH1") (class "Default")
      (node (ref "C11") (pin "2") (pinfunction "2_2") (pintype "passive"))
      (node (ref "HALL2") (pin "3") (pinfunction "S_3") (pintype "passive"))
      (node (ref "R23") (pin "2") (pinfunction "2_2") (pintype "passive"))
      (node (ref "U1") (pin "55") (pinfunction "PB3_55") (pintype "bidirectional"))
    )
    (net (code "68") (name "TIM8_CH1") (class "Default")
      (node (ref "C21") (pin "2") (pinfunction "2_2") (pintype "passive"))
      (node (ref "HALL1") (pin "3") (pinfunction "S_3") (pintype "passive"))
      (node (ref "R22") (pin "2") (pinfunction "2_2") (pintype "passive"))
      (node (ref "U1") (pin "37") (pinfunction "PC6_37") (pintype "bidirectional"))
    )
    (net (code "69") (name "USART1_CK") (class "Default")
      (node (ref "U1") (pin "41") (pinfunction "PA8_41") (pintype "bidirectional"))
    )
    (net (code "70") (name "USART1_RX") (class "Default")
      (node (ref "2N2222") (pin "C") (pinfunction "C_C") (pintype "passive"))
      (node (ref "R17") (pin "2") (pinfunction "2_2") (pintype "passive"))
      (node (ref "U1") (pin "43") (pinfunction "PA10_43") (pintype "bidirectional"))
    )
    (net (code "71") (name "USART1_TX") (class "Default")
      (node (ref "U1") (pin "42") (pinfunction "PA9_42") (pintype "bidirectional"))
    )
    (net (code "72") (name "USART3_CK") (class "Default")
      (node (ref "U1") (pin "53") (pinfunction "PC12_53") (pintype "bidirectional"))
    )
    (net (code "73") (name "USART3_RX") (class "Default")
      (node (ref "NL-652ETTL") (pin "4") (pinfunction "S_4") (pintype "passive"))
      (node (ref "U1") (pin "52") (pinfunction "PC11_52") (pintype "bidirectional"))
    )
    (net (code "74") (name "USART3_TX") (class "Default")
      (node (ref "R31") (pin "2") (pinfunction "2_2") (pintype "passive"))
      (node (ref "U1") (pin "51") (pinfunction "PC10_51") (pintype "bidirectional"))
    )
    (net (code "75") (name "V+") (class "Default")
      (node (ref "BAT60JFILM") (pin "A") (pinfunction "A_A") (pintype "passive"))
      (node (ref "C7") (pin "1") (pinfunction "1_1") (pintype "passive"))
      (node (ref "CH0") (pin "2") (pinfunction "2_2") (pintype "passive"))
      (node (ref "CH1") (pin "2") (pinfunction "2_2") (pintype "passive"))
      (node (ref "CH2") (pin "2") (pinfunction "2_2") (pintype "passive"))
      (node (ref "CH3") (pin "2") (pinfunction "2_2") (pintype "passive"))
      (node (ref "CH4") (pin "2") (pinfunction "2_2") (pintype "passive"))
      (node (ref "CH5") (pin "2") (pinfunction "2_2") (pintype "passive"))
      (node (ref "CH6") (pin "2") (pinfunction "2_2") (pintype "passive"))
      (node (ref "CH7") (pin "2") (pinfunction "2_2") (pintype "passive"))
    )
    (net (code "76") (name "VBAT_S") (class "Default")
      (node (ref "R29") (pin "1") (pinfunction "1_1") (pintype "passive"))
      (node (ref "R30") (pin "1") (pinfunction "1_1") (pintype "passive"))
      (node (ref "U1") (pin "8") (pinfunction "PC0_8") (pintype "bidirectional"))
    )
    (net (code "77") (name "VCC") (class "Default")
      (node (ref "C10") (pin "1") (pinfunction "1_1") (pintype "passive"))
      (node (ref "C12") (pin "1") (pinfunction "1_1") (pintype "passive"))
      (node (ref "C13") (pin "1") (pinfunction "1_1") (pintype "passive"))
      (node (ref "C14") (pin "1") (pinfunction "1_1") (pintype "passive"))
      (node (ref "C15") (pin "1") (pinfunction "1_1") (pintype "passive"))
      (node (ref "C17") (pin "1") (pinfunction "1_1") (pintype "passive"))
      (node (ref "C18") (pin "1") (pinfunction "1_1") (pintype "passive"))
      (node (ref "C20") (pin "1") (pinfunction "1_1") (pintype "passive"))
      (node (ref "C4") (pin "2") (pinfunction "2_2") (pintype "passive"))
      (node (ref "C6") (pin "1") (pinfunction "1_1") (pintype "passive"))
      (node (ref "FCM1608-0603") (pin "1") (pinfunction "P$1_1") (pintype "bidirectional"))
      (node (ref "HALL1") (pin "1") (pinfunction "S_1") (pintype "passive"))
      (node (ref "HALL2") (pin "1") (pinfunction "S_1") (pintype "passive"))
      (node (ref "IC1") (pin "2") (pinfunction "VOUT_2") (pintype "power_in"))
      (node (ref "IMU_DROTEK") (pin "3") (pinfunction "S_3") (pintype "passive"))
      (node (ref "I_T_V") (pin "4") (pinfunction "S_4") (pintype "passive"))
      (node (ref "MAXSONAR") (pin "2") (pinfunction "S_2") (pintype "passive"))
      (node (ref "MAXSONAR") (pin "4") (pinfunction "S_4") (pintype "passive"))
      (node (ref "NL-652ETTL") (pin "1") (pinfunction "S_1") (pintype "passive"))
      (node (ref "NRF24L01+") (pin "2") (pinfunction "2_2") (pintype "passive"))
      (node (ref "R11") (pin "2") (pinfunction "2_2") (pintype "passive"))
      (node (ref "R17") (pin "1") (pinfunction "1_1") (pintype "passive"))
      (node (ref "R18") (pin "1") (pinfunction "1_1") (pintype "passive"))
      (node (ref "R20") (pin "2") (pinfunction "2_2") (pintype "passive"))
      (node (ref "R22") (pin "1") (pinfunction "1_1") (pintype "passive"))
      (node (ref "R23") (pin "1") (pinfunction "1_1") (pintype "passive"))
      (node (ref "R3") (pin "1") (pinfunction "1_1") (pintype "passive"))
      (node (ref "R9") (pin "1") (pinfunction "1_1") (pintype "passive"))
      (node (ref "SWD") (pin "1") (pinfunction "S_1") (pintype "passive"))
      (node (ref "U$3") (pin "5") (pinfunction "VCC_5") (pintype "bidirectional"))
      (node (ref "U1") (pin "1") (pinfunction "VBAT_1") (pintype "power_in"))
      (node (ref "U1") (pin "19") (pinfunction "VDD_4_19") (pintype "power_in"))
      (node (ref "U1") (pin "32") (pinfunction "VDD_1_32") (pintype "power_in"))
      (node (ref "U1") (pin "48") (pinfunction "VDD_2_48") (pintype "power_in"))
      (node (ref "U1") (pin "64") (pinfunction "VDD_3_64") (pintype "power_in"))
    )
    (net (code "78") (name "unconnected-(IMU_DROTEKB-S-Pad2)") (class "Default")
      (node (ref "IMU_DROTEK") (pin "2") (pinfunction "S_2") (pintype "passive"))
    )
    (net (code "79") (name "unconnected-(MAXSONARE-S-Pad5)") (class "Default")
      (node (ref "MAXSONAR") (pin "5") (pinfunction "S_5") (pintype "passive"))
    )
    (net (code "80") (name "unconnected-(MAXSONARF-S-Pad6)") (class "Default")
      (node (ref "MAXSONAR") (pin "6") (pinfunction "S_6") (pintype "passive"))
    )
    (net (code "81") (name "unconnected-(U$3-GPIO2-Pad8)") (class "Default")
      (node (ref "U$3") (pin "8") (pinfunction "GPIO2_8") (pintype "bidirectional"))
    )
    (net (code "82") (name "unconnected-(U1B-PA15-Pad50)") (class "Default")
      (node (ref "U1") (pin "50") (pinfunction "PA15_50") (pintype "bidirectional"))
    )
    (net (code "83") (name "unconnected-(U1E-PB0-Pad26)") (class "Default")
      (node (ref "U1") (pin "26") (pinfunction "PB0_26") (pintype "bidirectional"))
    )
    (net (code "84") (name "unconnected-(U1E-PB1-Pad27)") (class "Default")
      (node (ref "U1") (pin "27") (pinfunction "PB1_27") (pintype "bidirectional"))
    )
    (net (code "85") (name "unconnected-(U1E-PB4-Pad56)") (class "Default")
      (node (ref "U1") (pin "56") (pinfunction "PB4_56") (pintype "bidirectional"))
    )
    (net (code "86") (name "unconnected-(U1E-PB5-Pad57)") (class "Default")
      (node (ref "U1") (pin "57") (pinfunction "PB5_57") (pintype "bidirectional"))
    )
    (net (code "87") (name "unconnected-(U1F-PC13-Pad2)") (class "Default")
      (node (ref "U1") (pin "2") (pinfunction "PC13_2") (pintype "bidirectional"))
    )
    (net (code "88") (name "unconnected-(U1F-PC14-Pad3)") (class "Default")
      (node (ref "U1") (pin "3") (pinfunction "PC14_3") (pintype "bidirectional"))
    )
    (net (code "89") (name "unconnected-(U1F-PC15-Pad4)") (class "Default")
      (node (ref "U1") (pin "4") (pinfunction "PC15_4") (pintype "bidirectional"))
    )
    (net (code "90") (name "unconnected-(U1H-PD2-Pad54)") (class "Default")
      (node (ref "U1") (pin "54") (pinfunction "PD2_54") (pintype "bidirectional"))
    )
  )
)
